# ATtiny4313_PCA9543_Test.net
KiCad netlist of a schematic drawn in EAGLE
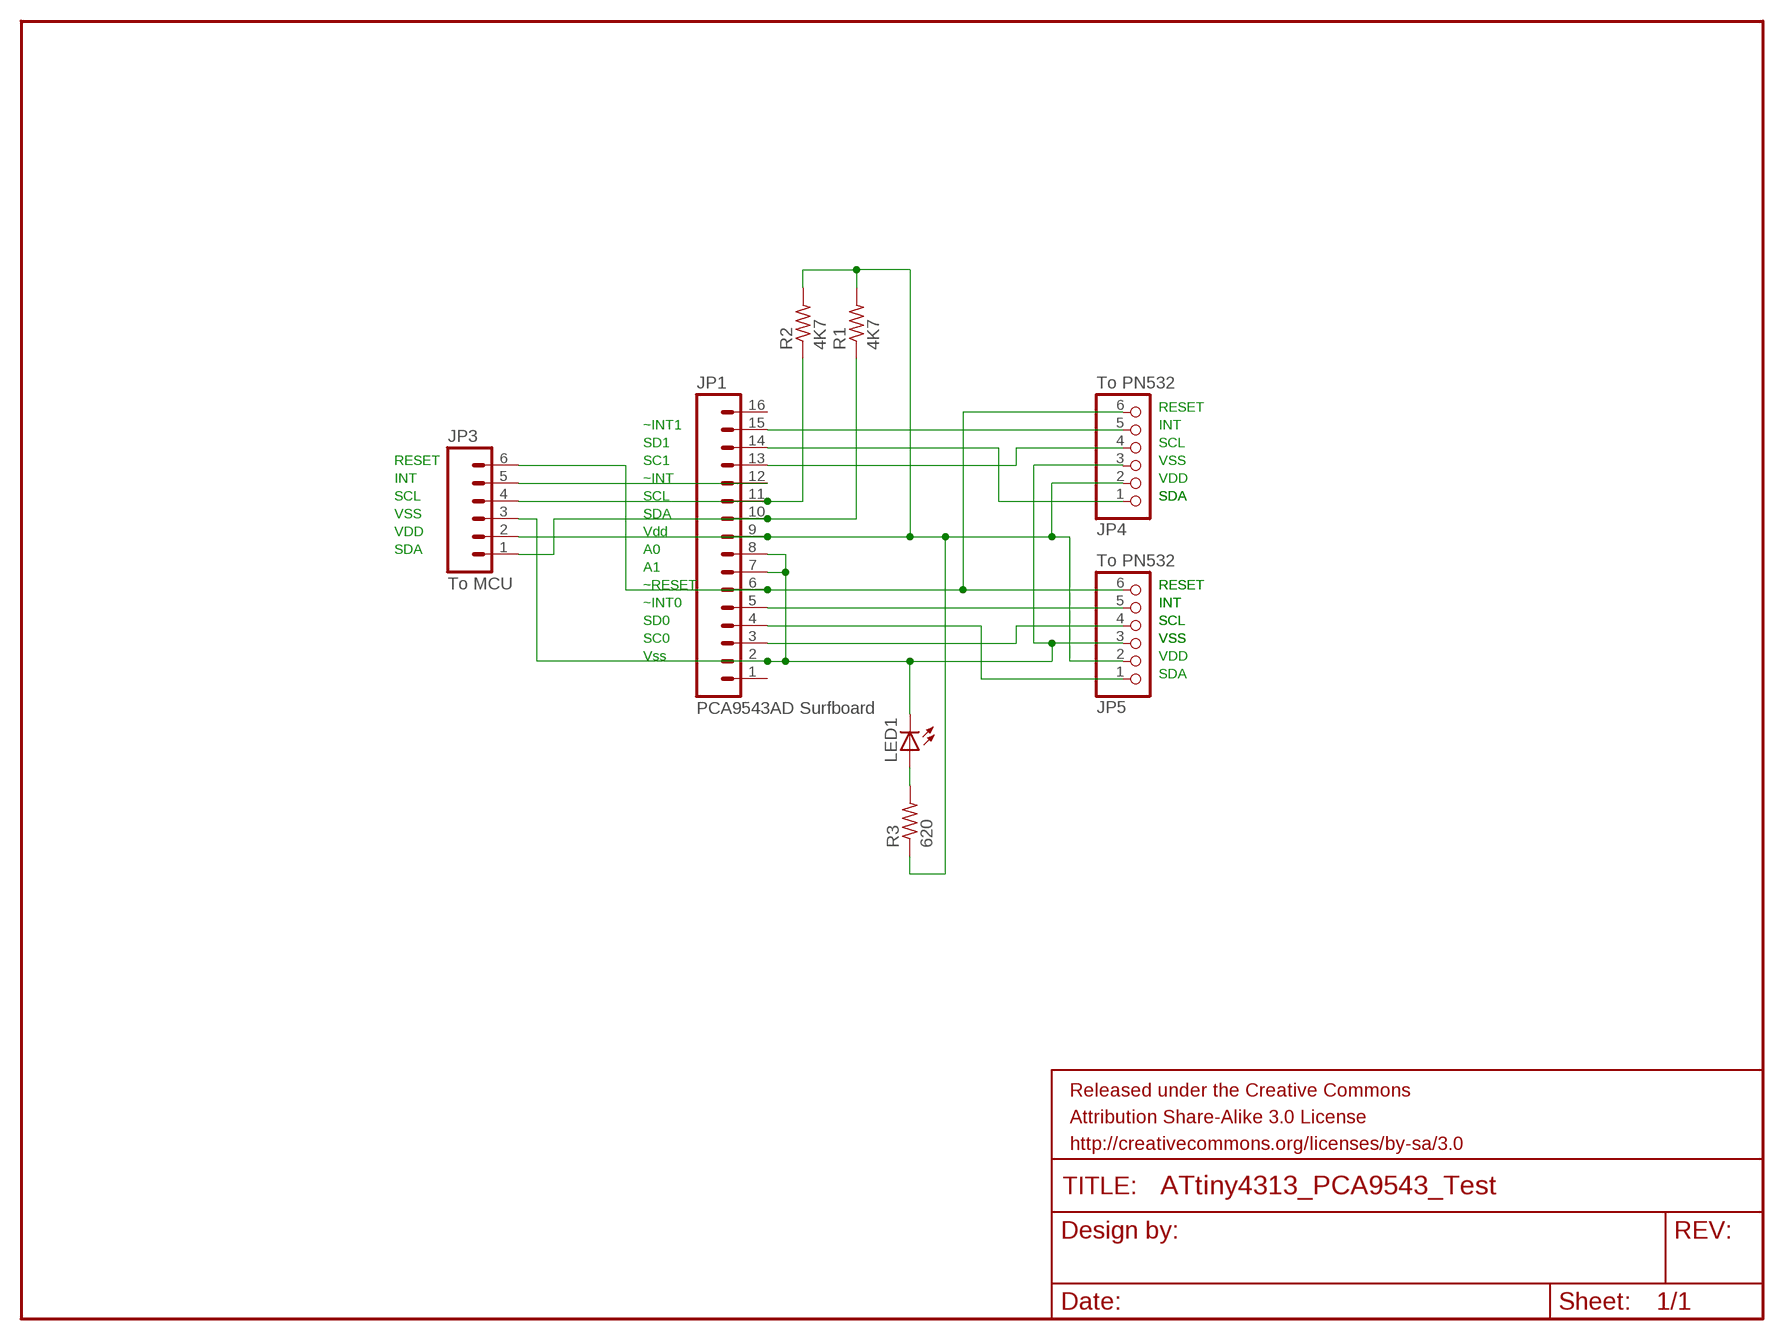
[diagram p0: schematic, sheet 1]

(export (version "E")
  (design (tool "Eeschema 10.0.6"))
  (components
    (comp (ref "JP1")
      (value "PCA9543AD Surfboard")
      (footprint "eagle-import:1X16_MACHINE-PIN-HEADER_LOCK.004")
      (libsource (lib "eagle-import") (part "M16MACHIINE-PIN_LOCK"))
    )
    (comp (ref "JP3")
      (value "To MCU")
      (footprint "eagle-import:1X06_LONGPADS")
      (libsource (lib "eagle-import") (part "M06LONGPADS"))
    )
    (comp (ref "JP4")
      (value "To PN532")
      (footprint "eagle-import:1X06_90")
      (libsource (lib "eagle-import") (part "PINHD-1X6/90"))
    )
    (comp (ref "JP5")
      (value "To PN532")
      (footprint "eagle-import:1X06_90")
      (libsource (lib "eagle-import") (part "PINHD-1X6/90"))
    )
    (comp (ref "LED1")
      (value "LED5MM")
      (footprint "eagle-import:LED5MM")
      (libsource (lib "eagle-import") (part "LED5MM"))
    )
    (comp (ref "R1")
      (value "4K7")
      (footprint "eagle-import:0204_5")
      (libsource (lib "eagle-import") (part "R-US_0204/5"))
    )
    (comp (ref "R2")
      (value "4K7")
      (footprint "eagle-import:0204_5")
      (libsource (lib "eagle-import") (part "R-US_0204/5"))
    )
    (comp (ref "R3")
      (value "620")
      (footprint "eagle-import:0309_12")
      (libsource (lib "eagle-import") (part "R-US_0309/12"))
    )
  )
  (nets
    (net (code "1") (name "Net-(JP1-Pad3)") (class "Default")
      (node (ref "JP1") (pin "3") (pinfunction "3_3") (pintype "passive"))
      (node (ref "JP5") (pin "4") (pinfunction "4_4") (pintype "passive"))
    )
    (net (code "2") (name "Net-(JP1-Pad4)") (class "Default")
      (node (ref "JP1") (pin "4") (pinfunction "4_4") (pintype "passive"))
      (node (ref "JP5") (pin "1") (pinfunction "1_1") (pintype "passive"))
    )
    (net (code "3") (name "Net-(JP1-Pad5)") (class "Default")
      (node (ref "JP1") (pin "5") (pinfunction "5_5") (pintype "passive"))
      (node (ref "JP5") (pin "5") (pinfunction "5_5") (pintype "passive"))
    )
    (net (code "4") (name "Net-(JP1-Pad6)") (class "Default")
      (node (ref "JP1") (pin "6") (pinfunction "6_6") (pintype "passive"))
      (node (ref "JP3") (pin "6") (pinfunction "6_6") (pintype "passive"))
      (node (ref "JP4") (pin "6") (pinfunction "6_6") (pintype "passive"))
      (node (ref "JP5") (pin "6") (pinfunction "6_6") (pintype "passive"))
    )
    (net (code "5") (name "Net-(JP1-Pad9)") (class "Default")
      (node (ref "JP1") (pin "9") (pinfunction "9_9") (pintype "passive"))
      (node (ref "JP3") (pin "2") (pinfunction "2_2") (pintype "passive"))
      (node (ref "JP4") (pin "2") (pinfunction "2_2") (pintype "passive"))
      (node (ref "JP5") (pin "2") (pinfunction "2_2") (pintype "passive"))
      (node (ref "R1") (pin "2") (pinfunction "2_2") (pintype "passive"))
      (node (ref "R2") (pin "2") (pinfunction "2_2") (pintype "passive"))
      (node (ref "R3") (pin "1") (pinfunction "1_1") (pintype "passive"))
    )
    (net (code "6") (name "Net-(JP1-Pad10)") (class "Default")
      (node (ref "JP1") (pin "10") (pinfunction "10_10") (pintype "passive"))
      (node (ref "JP3") (pin "1") (pinfunction "1_1") (pintype "passive"))
      (node (ref "R1") (pin "1") (pinfunction "1_1") (pintype "passive"))
    )
    (net (code "7") (name "Net-(JP1-Pad11)") (class "Default")
      (node (ref "JP1") (pin "11") (pinfunction "11_11") (pintype "passive"))
      (node (ref "JP3") (pin "4") (pinfunction "4_4") (pintype "passive"))
      (node (ref "R2") (pin "1") (pinfunction "1_1") (pintype "passive"))
    )
    (net (code "8") (name "Net-(JP1-Pad12)") (class "Default")
      (node (ref "JP1") (pin "12") (pinfunction "12_12") (pintype "passive"))
      (node (ref "JP3") (pin "5") (pinfunction "5_5") (pintype "passive"))
    )
    (net (code "9") (name "Net-(JP1-Pad13)") (class "Default")
      (node (ref "JP1") (pin "13") (pinfunction "13_13") (pintype "passive"))
      (node (ref "JP4") (pin "4") (pinfunction "4_4") (pintype "passive"))
    )
    (net (code "10") (name "Net-(JP1-Pad14)") (class "Default")
      (node (ref "JP1") (pin "14") (pinfunction "14_14") (pintype "passive"))
      (node (ref "JP4") (pin "1") (pinfunction "1_1") (pintype "passive"))
    )
    (net (code "11") (name "Net-(JP1-Pad15)") (class "Default")
      (node (ref "JP1") (pin "15") (pinfunction "15_15") (pintype "passive"))
      (node (ref "JP4") (pin "5") (pinfunction "5_5") (pintype "passive"))
    )
    (net (code "12") (name "Net-(LED1-C)") (class "Default")
      (node (ref "JP1") (pin "2") (pinfunction "2_2") (pintype "passive"))
      (node (ref "JP1") (pin "7") (pinfunction "7_7") (pintype "passive"))
      (node (ref "JP1") (pin "8") (pinfunction "8_8") (pintype "passive"))
      (node (ref "JP3") (pin "3") (pinfunction "3_3") (pintype "passive"))
      (node (ref "JP4") (pin "3") (pinfunction "3_3") (pintype "passive"))
      (node (ref "JP5") (pin "3") (pinfunction "3_3") (pintype "passive"))
      (node (ref "LED1") (pin "K") (pinfunction "C_K") (pintype "passive"))
    )
    (net (code "13") (name "Net-(LED1-PadA)") (class "Default")
      (node (ref "LED1") (pin "A") (pinfunction "A_A") (pintype "passive"))
      (node (ref "R3") (pin "2") (pinfunction "2_2") (pintype "passive"))
    )
    (net (code "14") (name "unconnected-(JP1-Pad1)") (class "Default")
      (node (ref "JP1") (pin "1") (pinfunction "1_1") (pintype "passive"))
    )
    (net (code "15") (name "unconnected-(JP1-Pad16)") (class "Default")
      (node (ref "JP1") (pin "16") (pinfunction "16_16") (pintype "passive"))
    )
  )
)
